# CatchTheLightV2_0.net
KiCad netlist of a schematic drawn in EAGLE
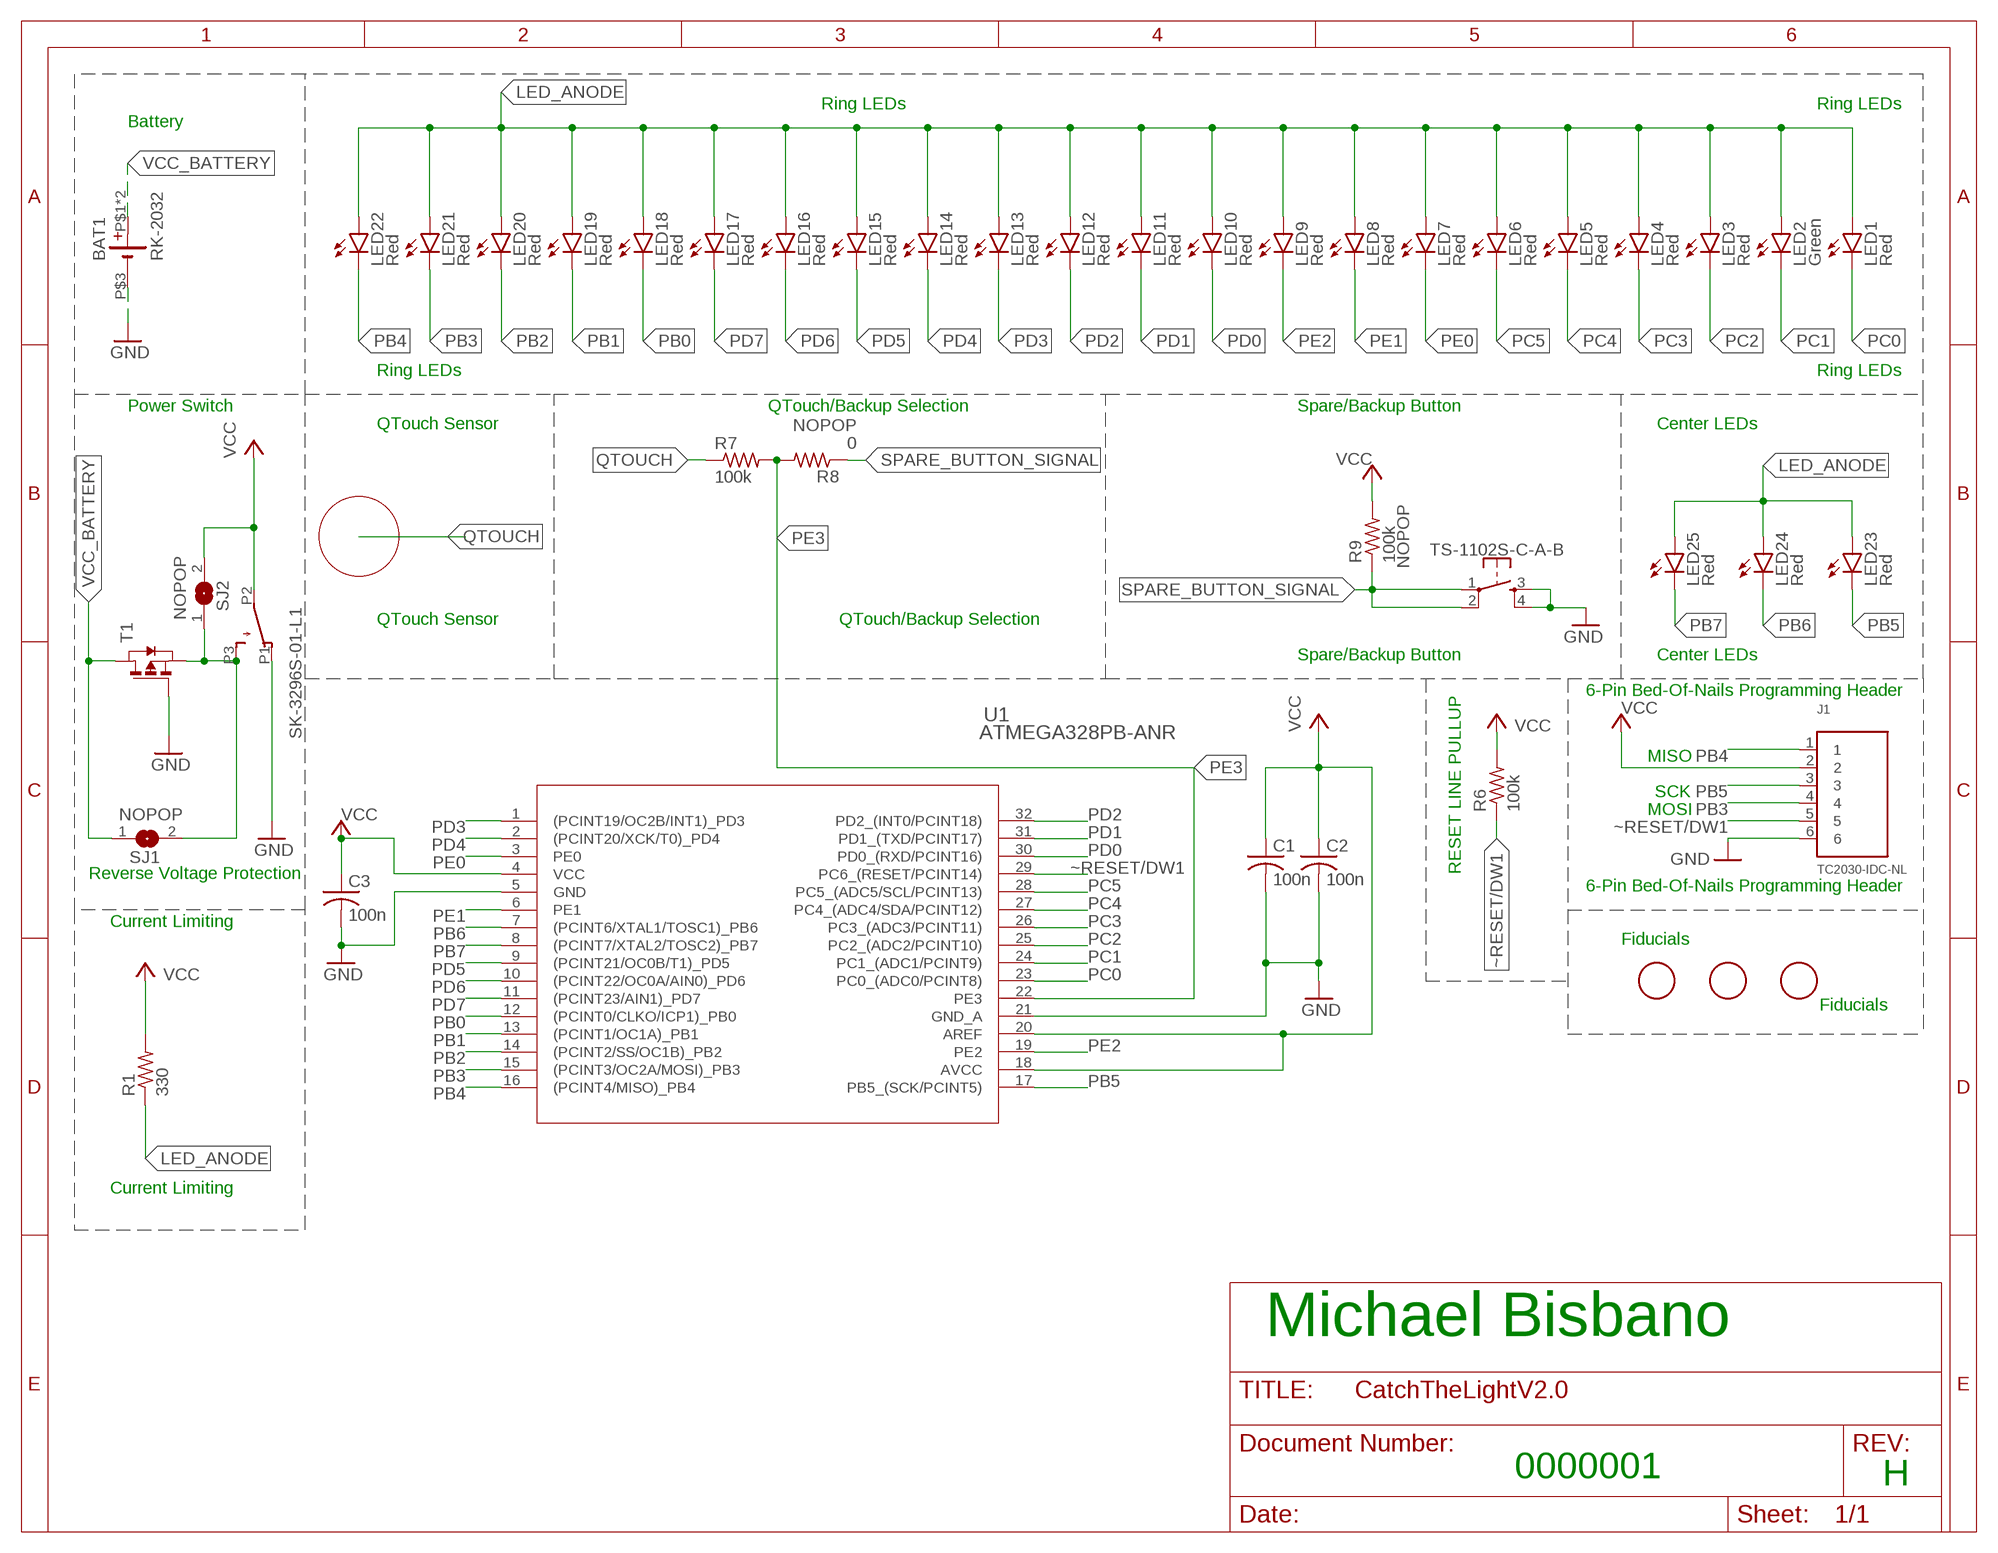
[diagram p0: schematic, sheet 1]

(export (version "E")
  (design (tool "Eeschema 10.0.6"))
  (components
    (comp (ref "BAT1")
      (value "RK-2032")
      (footprint "eagle-import:RK-2032")
      (libsource (lib "eagle-import") (part "RK-2032"))
    )
    (comp (ref "C1")
      (value "100n")
      (footprint "eagle-import:CAPC2012X110")
      (libsource (lib "eagle-import") (part "C-USCHIP-0805(2012-METRIC)_"))
    )
    (comp (ref "C2")
      (value "100n")
      (footprint "eagle-import:CAPC2012X110")
      (libsource (lib "eagle-import") (part "C-USCHIP-0805(2012-METRIC)_"))
    )
    (comp (ref "C3")
      (value "100n")
      (footprint "eagle-import:CAPC2012X110")
      (libsource (lib "eagle-import") (part "C-USCHIP-0805(2012-METRIC)_"))
    )
    (comp (ref "J1")
      (value "TC2030-IDC-NL")
      (footprint "eagle-import:TAG_TC2030-IDC-NL")
      (fields (field (name "MF") "Tag-Connect"))
      (libsource (lib "eagle-import") (part "TC2030-IDC-NL"))
    )
    (comp (ref "LED1")
      (value "Red")
      (footprint "eagle-import:CHIP-LED0805")
      (libsource (lib "eagle-import") (part "LEDCHIP-LED0805"))
    )
    (comp (ref "LED2")
      (value "Green")
      (footprint "eagle-import:CHIP-LED0805")
      (libsource (lib "eagle-import") (part "LEDCHIP-LED0805"))
    )
    (comp (ref "LED3")
      (value "Red")
      (footprint "eagle-import:CHIP-LED0805")
      (libsource (lib "eagle-import") (part "LEDCHIP-LED0805"))
    )
    (comp (ref "LED4")
      (value "Red")
      (footprint "eagle-import:CHIP-LED0805")
      (libsource (lib "eagle-import") (part "LEDCHIP-LED0805"))
    )
    (comp (ref "LED5")
      (value "Red")
      (footprint "eagle-import:CHIP-LED0805")
      (libsource (lib "eagle-import") (part "LEDCHIP-LED0805"))
    )
    (comp (ref "LED6")
      (value "Red")
      (footprint "eagle-import:CHIP-LED0805")
      (libsource (lib "eagle-import") (part "LEDCHIP-LED0805"))
    )
    (comp (ref "LED7")
      (value "Red")
      (footprint "eagle-import:CHIP-LED0805")
      (libsource (lib "eagle-import") (part "LEDCHIP-LED0805"))
    )
    (comp (ref "LED8")
      (value "Red")
      (footprint "eagle-import:CHIP-LED0805")
      (libsource (lib "eagle-import") (part "LEDCHIP-LED0805"))
    )
    (comp (ref "LED9")
      (value "Red")
      (footprint "eagle-import:CHIP-LED0805")
      (libsource (lib "eagle-import") (part "LEDCHIP-LED0805"))
    )
    (comp (ref "LED10")
      (value "Red")
      (footprint "eagle-import:CHIP-LED0805")
      (libsource (lib "eagle-import") (part "LEDCHIP-LED0805"))
    )
    (comp (ref "LED11")
      (value "Red")
      (footprint "eagle-import:CHIP-LED0805")
      (libsource (lib "eagle-import") (part "LEDCHIP-LED0805"))
    )
    (comp (ref "LED12")
      (value "Red")
      (footprint "eagle-import:CHIP-LED0805")
      (libsource (lib "eagle-import") (part "LEDCHIP-LED0805"))
    )
    (comp (ref "LED13")
      (value "Red")
      (footprint "eagle-import:CHIP-LED0805")
      (libsource (lib "eagle-import") (part "LEDCHIP-LED0805"))
    )
    (comp (ref "LED14")
      (value "Red")
      (footprint "eagle-import:CHIP-LED0805")
      (libsource (lib "eagle-import") (part "LEDCHIP-LED0805"))
    )
    (comp (ref "LED15")
      (value "Red")
      (footprint "eagle-import:CHIP-LED0805")
      (libsource (lib "eagle-import") (part "LEDCHIP-LED0805"))
    )
    (comp (ref "LED16")
      (value "Red")
      (footprint "eagle-import:CHIP-LED0805")
      (libsource (lib "eagle-import") (part "LEDCHIP-LED0805"))
    )
    (comp (ref "LED17")
      (value "Red")
      (footprint "eagle-import:CHIP-LED0805")
      (libsource (lib "eagle-import") (part "LEDCHIP-LED0805"))
    )
    (comp (ref "LED18")
      (value "Red")
      (footprint "eagle-import:CHIP-LED0805")
      (libsource (lib "eagle-import") (part "LEDCHIP-LED0805"))
    )
    (comp (ref "LED19")
      (value "Red")
      (footprint "eagle-import:CHIP-LED0805")
      (libsource (lib "eagle-import") (part "LEDCHIP-LED0805"))
    )
    (comp (ref "LED20")
      (value "Red")
      (footprint "eagle-import:CHIP-LED0805")
      (libsource (lib "eagle-import") (part "LEDCHIP-LED0805"))
    )
    (comp (ref "LED21")
      (value "Red")
      (footprint "eagle-import:CHIP-LED0805")
      (libsource (lib "eagle-import") (part "LEDCHIP-LED0805"))
    )
    (comp (ref "LED22")
      (value "Red")
      (footprint "eagle-import:CHIP-LED0805")
      (libsource (lib "eagle-import") (part "LEDCHIP-LED0805"))
    )
    (comp (ref "LED23")
      (value "Red")
      (footprint "eagle-import:CHIP-LED0805")
      (libsource (lib "eagle-import") (part "LEDCHIP-LED0805"))
    )
    (comp (ref "LED24")
      (value "Red")
      (footprint "eagle-import:CHIP-LED0805")
      (libsource (lib "eagle-import") (part "LEDCHIP-LED0805"))
    )
    (comp (ref "LED25")
      (value "Red")
      (footprint "eagle-import:CHIPLED_0805")
      (libsource (lib "eagle-import") (part "LEDCHIPLED_0805"))
    )
    (comp (ref "PB1")
      (value "SK-3296S-01-L1")
      (footprint "eagle-import:SK-3296S-01-L1")
      (libsource (lib "eagle-import") (part "SK-3296S-01-L1"))
    )
    (comp (ref "PB2")
      (value "PB2")
      (footprint "eagle-import:TS-1102S-C-A-B")
      (libsource (lib "eagle-import") (part "TS-1102S-C-A-B"))
    )
    (comp (ref "R1")
      (value "330")
      (footprint "eagle-import:R0805")
      (libsource (lib "eagle-import") (part "R-US_R0805"))
    )
    (comp (ref "R6")
      (value "100k")
      (footprint "eagle-import:R0805")
      (libsource (lib "eagle-import") (part "R-US_R0805"))
    )
    (comp (ref "R7")
      (value "100k")
      (footprint "eagle-import:R0805")
      (libsource (lib "eagle-import") (part "R-US_R0805"))
    )
    (comp (ref "R8")
      (value "0")
      (footprint "eagle-import:R0805")
      (fields (field (name "NOPOP") "NOPOP"))
      (libsource (lib "eagle-import") (part "R-US_R0805"))
    )
    (comp (ref "R9")
      (value "100k")
      (footprint "eagle-import:R0805")
      (fields (field (name "NOPOP") "NOPOP"))
      (libsource (lib "eagle-import") (part "R-US_R0805"))
    )
    (comp (ref "SJ1")
      (value "NOPOP")
      (footprint "eagle-import:SJW")
      (libsource (lib "eagle-import") (part "SJW"))
    )
    (comp (ref "SJ2")
      (value "NOPOP")
      (footprint "eagle-import:SJW")
      (libsource (lib "eagle-import") (part "SJW"))
    )
    (comp (ref "T1")
      (value "PMOSSOT23")
      (footprint "eagle-import:SOT-23")
      (libsource (lib "eagle-import") (part "PMOSSOT23"))
    )
    (comp (ref "U$4")
      (value "FIDUCIAL")
      (footprint "eagle-import:FIDUCIAL_1MM")
      (libsource (lib "eagle-import") (part "FIDUCIAL"))
    )
    (comp (ref "U$5")
      (value "FIDUCIAL")
      (footprint "eagle-import:FIDUCIAL_1MM")
      (libsource (lib "eagle-import") (part "FIDUCIAL"))
    )
    (comp (ref "U$6")
      (value "FIDUCIAL")
      (footprint "eagle-import:FIDUCIAL_1MM")
      (libsource (lib "eagle-import") (part "FIDUCIAL"))
    )
    (comp (ref "U1")
      (value "ATMEGA328PB-ANR")
      (footprint "eagle-import:32A_MCH")
      (fields (field (name "COPYRIGHT") "Copyright (C) 2018 Accelerated Designs. All rights reserved"))
      (libsource (lib "eagle-import") (part "ATMEGA328PB-ANR"))
    )
  )
  (nets
    (net (code "1") (name "/~{RESET{slash}DW1}") (class "Default")
      (node (ref "J1") (pin "5") (pinfunction "5_5") (pintype "passive"))
      (node (ref "R6") (pin "1") (pinfunction "1_1") (pintype "passive"))
      (node (ref "U1") (pin "29") (pinfunction "PC6_(RESET/PCINT14)_29") (pintype "bidirectional"))
    )
    (net (code "2") (name "GND") (class "Default")
      (node (ref "BAT1") (pin "P$3") (pinfunction "-_P$3") (pintype "passive"))
      (node (ref "C1") (pin "2") (pinfunction "2_2") (pintype "passive"))
      (node (ref "C2") (pin "2") (pinfunction "2_2") (pintype "passive"))
      (node (ref "C3") (pin "2") (pinfunction "2_2") (pintype "passive"))
      (node (ref "J1") (pin "6") (pinfunction "6_6") (pintype "passive"))
      (node (ref "PB1") (pin "P1") (pinfunction "1_P1") (pintype "passive"))
      (node (ref "PB2") (pin "3") (pinfunction "3_3") (pintype "passive"))
      (node (ref "PB2") (pin "4") (pinfunction "4_4") (pintype "passive"))
      (node (ref "T1") (pin "3") (pinfunction "G_3") (pintype "passive"))
      (node (ref "U1") (pin "21") (pinfunction "GND_A_21") (pintype "power_in"))
      (node (ref "U1") (pin "5") (pinfunction "GND_5") (pintype "power_in"))
    )
    (net (code "3") (name "LED_ANODE") (class "Default")
      (node (ref "LED1") (pin "A") (pinfunction "A_A") (pintype "passive"))
      (node (ref "LED10") (pin "A") (pinfunction "A_A") (pintype "passive"))
      (node (ref "LED11") (pin "A") (pinfunction "A_A") (pintype "passive"))
      (node (ref "LED12") (pin "A") (pinfunction "A_A") (pintype "passive"))
      (node (ref "LED13") (pin "A") (pinfunction "A_A") (pintype "passive"))
      (node (ref "LED14") (pin "A") (pinfunction "A_A") (pintype "passive"))
      (node (ref "LED15") (pin "A") (pinfunction "A_A") (pintype "passive"))
      (node (ref "LED16") (pin "A") (pinfunction "A_A") (pintype "passive"))
      (node (ref "LED17") (pin "A") (pinfunction "A_A") (pintype "passive"))
      (node (ref "LED18") (pin "A") (pinfunction "A_A") (pintype "passive"))
      (node (ref "LED19") (pin "A") (pinfunction "A_A") (pintype "passive"))
      (node (ref "LED2") (pin "A") (pinfunction "A_A") (pintype "passive"))
      (node (ref "LED20") (pin "A") (pinfunction "A_A") (pintype "passive"))
      (node (ref "LED21") (pin "A") (pinfunction "A_A") (pintype "passive"))
      (node (ref "LED22") (pin "A") (pinfunction "A_A") (pintype "passive"))
      (node (ref "LED23") (pin "A") (pinfunction "A_A") (pintype "passive"))
      (node (ref "LED24") (pin "A") (pinfunction "A_A") (pintype "passive"))
      (node (ref "LED25") (pin "A") (pinfunction "A_A") (pintype "passive"))
      (node (ref "LED3") (pin "A") (pinfunction "A_A") (pintype "passive"))
      (node (ref "LED4") (pin "A") (pinfunction "A_A") (pintype "passive"))
      (node (ref "LED5") (pin "A") (pinfunction "A_A") (pintype "passive"))
      (node (ref "LED6") (pin "A") (pinfunction "A_A") (pintype "passive"))
      (node (ref "LED7") (pin "A") (pinfunction "A_A") (pintype "passive"))
      (node (ref "LED8") (pin "A") (pinfunction "A_A") (pintype "passive"))
      (node (ref "LED9") (pin "A") (pinfunction "A_A") (pintype "passive"))
      (node (ref "R1") (pin "1") (pinfunction "1_1") (pintype "passive"))
    )
    (net (code "4") (name "Net-(PB1-3)") (class "Default")
      (node (ref "PB1") (pin "P3") (pinfunction "3_P3") (pintype "passive"))
      (node (ref "SJ1") (pin "2") (pinfunction "2_2") (pintype "passive"))
      (node (ref "SJ2") (pin "1") (pinfunction "1_1") (pintype "passive"))
      (node (ref "T1") (pin "2") (pinfunction "S_2") (pintype "passive"))
    )
    (net (code "5") (name "PB0") (class "Default")
      (node (ref "LED18") (pin "C") (pinfunction "C_C") (pintype "passive"))
      (node (ref "U1") (pin "12") (pinfunction "(PCINT0/CLKO/ICP1)_PB0_12") (pintype "bidirectional"))
    )
    (net (code "6") (name "PB1") (class "Default")
      (node (ref "LED19") (pin "C") (pinfunction "C_C") (pintype "passive"))
      (node (ref "U1") (pin "13") (pinfunction "(PCINT1/OC1A)_PB1_13") (pintype "bidirectional"))
    )
    (net (code "7") (name "PB2") (class "Default")
      (node (ref "LED20") (pin "C") (pinfunction "C_C") (pintype "passive"))
      (node (ref "U1") (pin "14") (pinfunction "(PCINT2/SS/OC1B)_PB2_14") (pintype "bidirectional"))
    )
    (net (code "8") (name "PB3") (class "Default")
      (node (ref "J1") (pin "4") (pinfunction "4_4") (pintype "passive"))
      (node (ref "LED21") (pin "C") (pinfunction "C_C") (pintype "passive"))
      (node (ref "U1") (pin "15") (pinfunction "(PCINT3/OC2A/MOSI)_PB3_15") (pintype "bidirectional"))
    )
    (net (code "9") (name "PB4") (class "Default")
      (node (ref "J1") (pin "1") (pinfunction "1_1") (pintype "passive"))
      (node (ref "LED22") (pin "C") (pinfunction "C_C") (pintype "passive"))
      (node (ref "U1") (pin "16") (pinfunction "(PCINT4/MISO)_PB4_16") (pintype "bidirectional"))
    )
    (net (code "10") (name "PB5") (class "Default")
      (node (ref "J1") (pin "3") (pinfunction "3_3") (pintype "passive"))
      (node (ref "LED23") (pin "C") (pinfunction "C_C") (pintype "passive"))
      (node (ref "U1") (pin "17") (pinfunction "PB5_(SCK/PCINT5)_17") (pintype "bidirectional"))
    )
    (net (code "11") (name "PB6") (class "Default")
      (node (ref "LED24") (pin "C") (pinfunction "C_C") (pintype "passive"))
      (node (ref "U1") (pin "7") (pinfunction "(PCINT6/XTAL1/TOSC1)_PB6_7") (pintype "bidirectional"))
    )
    (net (code "12") (name "PB7") (class "Default")
      (node (ref "LED25") (pin "C") (pinfunction "C_C") (pintype "passive"))
      (node (ref "U1") (pin "8") (pinfunction "(PCINT7/XTAL2/TOSC2)_PB7_8") (pintype "bidirectional"))
    )
    (net (code "13") (name "PC0") (class "Default")
      (node (ref "LED1") (pin "C") (pinfunction "C_C") (pintype "passive"))
      (node (ref "U1") (pin "23") (pinfunction "PC0_(ADC0/PCINT8)_23") (pintype "bidirectional"))
    )
    (net (code "14") (name "PC1") (class "Default")
      (node (ref "LED2") (pin "C") (pinfunction "C_C") (pintype "passive"))
      (node (ref "U1") (pin "24") (pinfunction "PC1_(ADC1/PCINT9)_24") (pintype "bidirectional"))
    )
    (net (code "15") (name "PC2") (class "Default")
      (node (ref "LED3") (pin "C") (pinfunction "C_C") (pintype "passive"))
      (node (ref "U1") (pin "25") (pinfunction "PC2_(ADC2/PCINT10)_25") (pintype "bidirectional"))
    )
    (net (code "16") (name "PC3") (class "Default")
      (node (ref "LED4") (pin "C") (pinfunction "C_C") (pintype "passive"))
      (node (ref "U1") (pin "26") (pinfunction "PC3_(ADC3/PCINT11)_26") (pintype "bidirectional"))
    )
    (net (code "17") (name "PC4") (class "Default")
      (node (ref "LED5") (pin "C") (pinfunction "C_C") (pintype "passive"))
      (node (ref "U1") (pin "27") (pinfunction "PC4_(ADC4/SDA/PCINT12)_27") (pintype "bidirectional"))
    )
    (net (code "18") (name "PC5") (class "Default")
      (node (ref "LED6") (pin "C") (pinfunction "C_C") (pintype "passive"))
      (node (ref "U1") (pin "28") (pinfunction "PC5_(ADC5/SCL/PCINT13)_28") (pintype "bidirectional"))
    )
    (net (code "19") (name "PD0") (class "Default")
      (node (ref "LED10") (pin "C") (pinfunction "C_C") (pintype "passive"))
      (node (ref "U1") (pin "30") (pinfunction "PD0_(RXD/PCINT16)_30") (pintype "bidirectional"))
    )
    (net (code "20") (name "PD1") (class "Default")
      (node (ref "LED11") (pin "C") (pinfunction "C_C") (pintype "passive"))
      (node (ref "U1") (pin "31") (pinfunction "PD1_(TXD/PCINT17)_31") (pintype "bidirectional"))
    )
    (net (code "21") (name "PD2") (class "Default")
      (node (ref "LED12") (pin "C") (pinfunction "C_C") (pintype "passive"))
      (node (ref "U1") (pin "32") (pinfunction "PD2_(INT0/PCINT18)_32") (pintype "bidirectional"))
    )
    (net (code "22") (name "PD3") (class "Default")
      (node (ref "LED13") (pin "C") (pinfunction "C_C") (pintype "passive"))
      (node (ref "U1") (pin "1") (pinfunction "(PCINT19/OC2B/INT1)_PD3_1") (pintype "bidirectional"))
    )
    (net (code "23") (name "PD4") (class "Default")
      (node (ref "LED14") (pin "C") (pinfunction "C_C") (pintype "passive"))
      (node (ref "U1") (pin "2") (pinfunction "(PCINT20/XCK/T0)_PD4_2") (pintype "bidirectional"))
    )
    (net (code "24") (name "PD5") (class "Default")
      (node (ref "LED15") (pin "C") (pinfunction "C_C") (pintype "passive"))
      (node (ref "U1") (pin "9") (pinfunction "(PCINT21/OC0B/T1)_PD5_9") (pintype "bidirectional"))
    )
    (net (code "25") (name "PD6") (class "Default")
      (node (ref "LED16") (pin "C") (pinfunction "C_C") (pintype "passive"))
      (node (ref "U1") (pin "10") (pinfunction "(PCINT22/OC0A/AIN0)_PD6_10") (pintype "bidirectional"))
    )
    (net (code "26") (name "PD7") (class "Default")
      (node (ref "LED17") (pin "C") (pinfunction "C_C") (pintype "passive"))
      (node (ref "U1") (pin "11") (pinfunction "(PCINT23/AIN1)_PD7_11") (pintype "bidirectional"))
    )
    (net (code "27") (name "PE0") (class "Default")
      (node (ref "LED7") (pin "C") (pinfunction "C_C") (pintype "passive"))
      (node (ref "U1") (pin "3") (pinfunction "PE0_3") (pintype "power_in"))
    )
    (net (code "28") (name "PE1") (class "Default")
      (node (ref "LED8") (pin "C") (pinfunction "C_C") (pintype "passive"))
      (node (ref "U1") (pin "6") (pinfunction "PE1_6") (pintype "power_in"))
    )
    (net (code "29") (name "PE2") (class "Default")
      (node (ref "LED9") (pin "C") (pinfunction "C_C") (pintype "passive"))
      (node (ref "U1") (pin "19") (pinfunction "PE2_19") (pintype "input"))
    )
    (net (code "30") (name "PE3") (class "Default")
      (node (ref "R7") (pin "2") (pinfunction "2_2") (pintype "passive"))
      (node (ref "R8") (pin "2") (pinfunction "2_2") (pintype "passive"))
      (node (ref "U1") (pin "22") (pinfunction "PE3_22") (pintype "input"))
    )
    (net (code "31") (name "QTOUCH") (class "Default")
      (node (ref "R7") (pin "1") (pinfunction "1_1") (pintype "passive"))
    )
    (net (code "32") (name "SPARE_BUTTON_SIGNAL") (class "Default")
      (node (ref "PB2") (pin "1") (pinfunction "1_1") (pintype "passive"))
      (node (ref "PB2") (pin "2") (pinfunction "2_2") (pintype "passive"))
      (node (ref "R8") (pin "1") (pinfunction "1_1") (pintype "passive"))
      (node (ref "R9") (pin "1") (pinfunction "1_1") (pintype "passive"))
    )
    (net (code "33") (name "VCC") (class "Default")
      (node (ref "C1") (pin "1") (pinfunction "1_1") (pintype "passive"))
      (node (ref "C2") (pin "1") (pinfunction "1_1") (pintype "passive"))
      (node (ref "C3") (pin "1") (pinfunction "1_1") (pintype "passive"))
      (node (ref "J1") (pin "2") (pinfunction "2_2") (pintype "passive"))
      (node (ref "PB1") (pin "P2") (pinfunction "2_P2") (pintype "passive"))
      (node (ref "R1") (pin "2") (pinfunction "2_2") (pintype "passive"))
      (node (ref "R6") (pin "2") (pinfunction "2_2") (pintype "passive"))
      (node (ref "R9") (pin "2") (pinfunction "2_2") (pintype "passive"))
      (node (ref "SJ2") (pin "2") (pinfunction "2_2") (pintype "passive"))
      (node (ref "U1") (pin "18") (pinfunction "AVCC_18") (pintype "power_in"))
      (node (ref "U1") (pin "20") (pinfunction "AREF_20") (pintype "passive"))
      (node (ref "U1") (pin "4") (pinfunction "VCC_4") (pintype "power_in"))
    )
    (net (code "34") (name "VCC_BATTERY") (class "Default")
      (node (ref "BAT1") (pin "P$1") (pinfunction "+_P$1") (pintype "passive"))
      (node (ref "BAT1") (pin "P$2") (pinfunction "+_P$2") (pintype "passive"))
      (node (ref "SJ1") (pin "1") (pinfunction "1_1") (pintype "passive"))
      (node (ref "T1") (pin "1") (pinfunction "D_1") (pintype "passive"))
    )
  )
)
